# MachLedNhayTheoNhacNhieuCot.net
KiCad netlist of a schematic drawn in Altium Designer
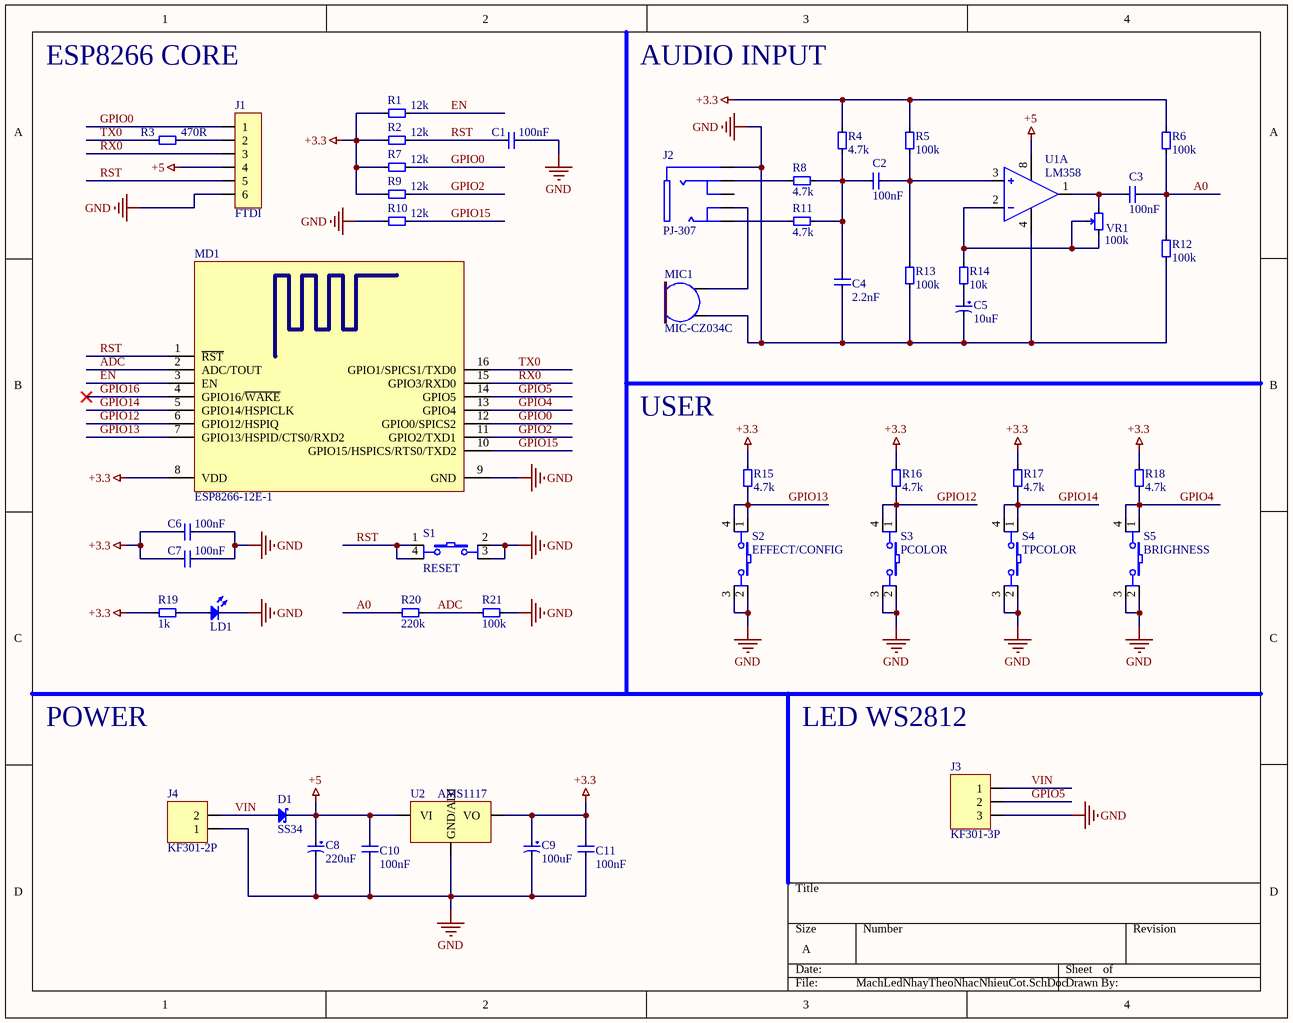
[diagram p0: MachLedNhayTheoNhacNhieuCot.SchDoc]

(export (version "E")
  (design (tool "Eeschema 10.0.6"))
  (components
    (comp (ref "C1")
      (value "100nF")
      (footprint "C-0805")
      (description "Cac Loai Tu Khong Phan Cuc")
      (libsource (lib "phatvu1294_Lib") (part "CAP"))
    )
    (comp (ref "C2")
      (value "100nF")
      (footprint "C-0805")
      (description "Cac Loai Tu Khong Phan Cuc")
      (libsource (lib "phatvu1294_Lib") (part "CAP"))
    )
    (comp (ref "C3")
      (value "100nF")
      (footprint "C-0805")
      (description "Cac Loai Tu Khong Phan Cuc")
      (libsource (lib "phatvu1294_Lib") (part "CAP"))
    )
    (comp (ref "C4")
      (value "2.2nF")
      (footprint "C-0805")
      (description "Cac Loai Tu Khong Phan Cuc")
      (libsource (lib "phatvu1294_Lib") (part "CAP"))
    )
    (comp (ref "C5")
      (value "10uF")
      (footprint "C-ELE-2-5X7MM")
      (description "Cac Loai Tu Hoa")
      (libsource (lib "phatvu1294_Lib") (part "CAP-ELE"))
    )
    (comp (ref "C6")
      (value "100nF")
      (footprint "C-0805")
      (description "Cac Loai Tu Khong Phan Cuc")
      (libsource (lib "phatvu1294_Lib") (part "CAP"))
    )
    (comp (ref "C7")
      (value "100nF")
      (footprint "C-0805")
      (description "Cac Loai Tu Khong Phan Cuc")
      (libsource (lib "phatvu1294_Lib") (part "CAP"))
    )
    (comp (ref "C8")
      (value "220uF")
      (footprint "C-ELE-2.5-6.3X12MM-A")
      (description "Cac Loai Tu Hoa")
      (libsource (lib "phatvu1294_Lib") (part "CAP-ELE"))
    )
    (comp (ref "C9")
      (value "100uF")
      (footprint "C-ELE-2.5-6.3X11MM-A")
      (description "Cac Loai Tu Hoa")
      (libsource (lib "phatvu1294_Lib") (part "CAP-ELE"))
    )
    (comp (ref "C10")
      (value "100nF")
      (footprint "C-0805")
      (description "Cac Loai Tu Khong Phan Cuc")
      (libsource (lib "phatvu1294_Lib") (part "CAP"))
    )
    (comp (ref "C11")
      (value "100nF")
      (footprint "C-0805")
      (description "Cac Loai Tu Khong Phan Cuc")
      (libsource (lib "phatvu1294_Lib") (part "CAP"))
    )
    (comp (ref "D1")
      (value "SS34")
      (footprint "DO-214AC-SMA")
      (description "Diode Schottky 1N5822 3A 40V Dan")
      (libsource (lib "phatvu1294_Lib") (part "SS34"))
    )
    (comp (ref "J1")
      (value "FTDI")
      (footprint "JP1X6M-2.54")
      (description "Jump Don 6 Chan 2.54mm")
      (libsource (lib "phatvu1294_Lib") (part "JP1X6-2.54"))
    )
    (comp (ref "J2")
      (value "PJ-307")
      (footprint "PJ-307")
      (description "Jack Ket Noi Audio 3.5MM")
      (libsource (lib "phatvu1294_Lib") (part "PJ-307"))
    )
    (comp (ref "J3")
      (value "KF301-3P")
      (footprint "KF301-3P-5.0")
      (description "Dau Ket Noi KF301 3 Chan")
      (libsource (lib "phatvu1294_Lib") (part "KF301-3P"))
    )
    (comp (ref "J4")
      (value "KF301-2P")
      (footprint "KF301-2P-5.0")
      (description "Dau Ket Noi KF301 2 Chan")
      (libsource (lib "phatvu1294_Lib") (part "KF301-2P"))
    )
    (comp (ref "LD1")
      (value "PWR")
      (footprint "LED-0805-RED")
      (description "Cac Loai LED Don")
      (libsource (lib "phatvu1294_Lib") (part "LED"))
    )
    (comp (ref "MD1")
      (value "ESP8266-12E-1")
      (footprint "ESP8266-12E-1")
      (description "Module ESP8266-12E")
      (libsource (lib "phatvu1294_Lib") (part "ESP8266-12E-1"))
    )
    (comp (ref "MIC1")
      (value "MIC-CZ034C")
      (footprint "MIC-CZ034C")
      (description "Microphone CZ034C")
      (libsource (lib "phatvu1294_Lib") (part "MIC-CZ034C"))
    )
    (comp (ref "R1")
      (value "12k")
      (footprint "R-0805")
      (description "Cac Loai Dien Tro")
      (libsource (lib "phatvu1294_Lib") (part "RES"))
    )
    (comp (ref "R2")
      (value "12k")
      (footprint "R-0805")
      (description "Cac Loai Dien Tro")
      (libsource (lib "phatvu1294_Lib") (part "RES"))
    )
    (comp (ref "R3")
      (value "470R")
      (footprint "R-0805")
      (description "Cac Loai Dien Tro")
      (libsource (lib "phatvu1294_Lib") (part "RES"))
    )
    (comp (ref "R4")
      (value "4.7k")
      (footprint "R-0805")
      (description "Cac Loai Dien Tro")
      (libsource (lib "phatvu1294_Lib") (part "RES"))
    )
    (comp (ref "R5")
      (value "100k")
      (footprint "R-0805")
      (description "Cac Loai Dien Tro")
      (libsource (lib "phatvu1294_Lib") (part "RES"))
    )
    (comp (ref "R6")
      (value "100k")
      (footprint "R-0805")
      (description "Cac Loai Dien Tro")
      (libsource (lib "phatvu1294_Lib") (part "RES"))
    )
    (comp (ref "R7")
      (value "12k")
      (footprint "R-0805")
      (description "Cac Loai Dien Tro")
      (libsource (lib "phatvu1294_Lib") (part "RES"))
    )
    (comp (ref "R8")
      (value "4.7k")
      (footprint "R-0805")
      (description "Cac Loai Dien Tro")
      (libsource (lib "phatvu1294_Lib") (part "RES"))
    )
    (comp (ref "R9")
      (value "12k")
      (footprint "R-0805")
      (description "Cac Loai Dien Tro")
      (libsource (lib "phatvu1294_Lib") (part "RES"))
    )
    (comp (ref "R10")
      (value "12k")
      (footprint "R-0805")
      (description "Cac Loai Dien Tro")
      (libsource (lib "phatvu1294_Lib") (part "RES"))
    )
    (comp (ref "R11")
      (value "4.7k")
      (footprint "R-0805")
      (description "Cac Loai Dien Tro")
      (libsource (lib "phatvu1294_Lib") (part "RES"))
    )
    (comp (ref "R12")
      (value "100k")
      (footprint "R-0805")
      (description "Cac Loai Dien Tro")
      (libsource (lib "phatvu1294_Lib") (part "RES"))
    )
    (comp (ref "R13")
      (value "100k")
      (footprint "R-0805")
      (description "Cac Loai Dien Tro")
      (libsource (lib "phatvu1294_Lib") (part "RES"))
    )
    (comp (ref "R14")
      (value "10k")
      (footprint "R-0805")
      (description "Cac Loai Dien Tro")
      (libsource (lib "phatvu1294_Lib") (part "RES"))
    )
    (comp (ref "R15")
      (value "4.7k")
      (footprint "R-0805")
      (description "Cac Loai Dien Tro")
      (libsource (lib "phatvu1294_Lib") (part "RES"))
    )
    (comp (ref "R16")
      (value "4.7k")
      (footprint "R-0805")
      (description "Cac Loai Dien Tro")
      (libsource (lib "phatvu1294_Lib") (part "RES"))
    )
    (comp (ref "R17")
      (value "4.7k")
      (footprint "R-0805")
      (description "Cac Loai Dien Tro")
      (libsource (lib "phatvu1294_Lib") (part "RES"))
    )
    (comp (ref "R18")
      (value "4.7k")
      (footprint "R-0805")
      (description "Cac Loai Dien Tro")
      (libsource (lib "phatvu1294_Lib") (part "RES"))
    )
    (comp (ref "R19")
      (value "1k")
      (footprint "R-0805")
      (description "Cac Loai Dien Tro")
      (libsource (lib "phatvu1294_Lib") (part "RES"))
    )
    (comp (ref "R20")
      (value "220k")
      (footprint "R-0805")
      (description "Cac Loai Dien Tro")
      (libsource (lib "phatvu1294_Lib") (part "RES"))
    )
    (comp (ref "R21")
      (value "100k")
      (footprint "R-0805")
      (description "Cac Loai Dien Tro")
      (libsource (lib "phatvu1294_Lib") (part "RES"))
    )
    (comp (ref "S1")
      (value "RESET")
      (footprint "SW4P-DIP-6X6MM")
      (description "Nut Nhan 4 Chan 6X6MM")
      (libsource (lib "phatvu1294_Lib") (part "SW4P-DIP-6X6MM"))
    )
    (comp (ref "S2")
      (value "EFFECT/CONFIG")
      (footprint "SW4P-DIP-6X6MM")
      (description "Nut Nhan 4 Chan 6X6MM")
      (libsource (lib "phatvu1294_Lib") (part "SW4P-DIP-6X6MM"))
    )
    (comp (ref "S3")
      (value "PCOLOR")
      (footprint "SW4P-DIP-6X6MM")
      (description "Nut Nhan 4 Chan 6X6MM")
      (libsource (lib "phatvu1294_Lib") (part "SW4P-DIP-6X6MM"))
    )
    (comp (ref "S4")
      (value "TPCOLOR")
      (footprint "SW4P-DIP-6X6MM")
      (description "Nut Nhan 4 Chan 6X6MM")
      (libsource (lib "phatvu1294_Lib") (part "SW4P-DIP-6X6MM"))
    )
    (comp (ref "S5")
      (value "BRIGHNESS")
      (footprint "SW4P-DIP-6X6MM")
      (description "Nut Nhan 4 Chan 6X6MM")
      (libsource (lib "phatvu1294_Lib") (part "SW4P-DIP-6X6MM"))
    )
    (comp (ref "U1")
      (value "LM358")
      (footprint "SO8-1.27-150MIL")
      (description "IC OPAM 2 Kenh")
      (libsource (lib "phatvu1294_Lib") (part "LM358"))
    )
    (comp (ref "U2")
      (value "AMS1117")
      (footprint "SOT223")
      (description "IC On Ap Tuyen Tinh AMS1117 1A")
      (libsource (lib "phatvu1294_Lib") (part "AMS1117"))
    )
    (comp (ref "VR1")
      (value "100k")
      (footprint "VR-ADJ-3362P")
      (description "Cac Loai Bien Tro")
      (libsource (lib "phatvu1294_Lib") (part "VRES"))
    )
  )
  (nets
    (net (code "1") (name "+3.3") (class "Default")
      (node (ref "C11") (pin "2") (pinfunction "2_2") (pintype "passive"))
      (node (ref "C6") (pin "2") (pinfunction "2_2") (pintype "passive"))
      (node (ref "C7") (pin "2") (pinfunction "2_2") (pintype "passive"))
      (node (ref "C9") (pin "1") (pinfunction "1_1") (pintype "passive"))
      (node (ref "MD1") (pin "8") (pinfunction "VDD_8") (pintype "power_in"))
      (node (ref "R1") (pin "1") (pinfunction "1_1") (pintype "passive"))
      (node (ref "R15") (pin "2") (pinfunction "2_2") (pintype "passive"))
      (node (ref "R16") (pin "2") (pinfunction "2_2") (pintype "passive"))
      (node (ref "R17") (pin "2") (pinfunction "2_2") (pintype "passive"))
      (node (ref "R18") (pin "2") (pinfunction "2_2") (pintype "passive"))
      (node (ref "R19") (pin "1") (pinfunction "1_1") (pintype "passive"))
      (node (ref "R2") (pin "1") (pinfunction "1_1") (pintype "passive"))
      (node (ref "R4") (pin "2") (pinfunction "2_2") (pintype "passive"))
      (node (ref "R5") (pin "2") (pinfunction "2_2") (pintype "passive"))
      (node (ref "R6") (pin "2") (pinfunction "2_2") (pintype "passive"))
      (node (ref "R7") (pin "1") (pinfunction "1_1") (pintype "passive"))
      (node (ref "R9") (pin "1") (pinfunction "1_1") (pintype "passive"))
      (node (ref "U2") (pin "2") (pinfunction "VO_2") (pintype "power_in"))
    )
    (net (code "2") (name "+5") (class "Default")
      (node (ref "C10") (pin "2") (pinfunction "2_2") (pintype "passive"))
      (node (ref "C8") (pin "1") (pinfunction "1_1") (pintype "passive"))
      (node (ref "D1") (pin "2") (pinfunction "2_2") (pintype "passive"))
      (node (ref "J1") (pin "4") (pinfunction "4_4") (pintype "passive"))
      (node (ref "U1") (pin "8") (pinfunction "V+_8") (pintype "power_in"))
      (node (ref "U2") (pin "3") (pinfunction "VI_3") (pintype "power_in"))
    )
    (net (code "3") (name "/A0") (class "Default")
      (node (ref "C3") (pin "2") (pinfunction "2_2") (pintype "passive"))
      (node (ref "R12") (pin "2") (pinfunction "2_2") (pintype "passive"))
      (node (ref "R20") (pin "1") (pinfunction "1_1") (pintype "passive"))
      (node (ref "R6") (pin "1") (pinfunction "1_1") (pintype "passive"))
    )
    (net (code "4") (name "/ADC") (class "Default")
      (node (ref "MD1") (pin "2") (pinfunction "ADC/TOUT_2") (pintype "passive"))
      (node (ref "R20") (pin "2") (pinfunction "2_2") (pintype "passive"))
      (node (ref "R21") (pin "1") (pinfunction "1_1") (pintype "passive"))
    )
    (net (code "5") (name "/EN") (class "Default")
      (node (ref "MD1") (pin "3") (pinfunction "EN_3") (pintype "passive"))
      (node (ref "R1") (pin "2") (pinfunction "2_2") (pintype "passive"))
    )
    (net (code "6") (name "/GPIO0") (class "Default")
      (node (ref "J1") (pin "1") (pinfunction "1_1") (pintype "passive"))
      (node (ref "MD1") (pin "12") (pinfunction "GPIO0/SPICS2_12") (pintype "passive"))
      (node (ref "R7") (pin "2") (pinfunction "2_2") (pintype "passive"))
    )
    (net (code "7") (name "/GPIO2") (class "Default")
      (node (ref "MD1") (pin "11") (pinfunction "GPIO2/TXD1_11") (pintype "passive"))
      (node (ref "R9") (pin "2") (pinfunction "2_2") (pintype "passive"))
    )
    (net (code "8") (name "/GPIO4") (class "Default")
      (node (ref "MD1") (pin "13") (pinfunction "GPIO4_13") (pintype "passive"))
      (node (ref "R18") (pin "1") (pinfunction "1_1") (pintype "passive"))
      (node (ref "S5") (pin "1") (pinfunction "1_1") (pintype "passive"))
      (node (ref "S5") (pin "4") (pinfunction "4_4") (pintype "passive"))
    )
    (net (code "9") (name "/GPIO5") (class "Default")
      (node (ref "J3") (pin "2") (pinfunction "2_2") (pintype "passive"))
      (node (ref "MD1") (pin "14") (pinfunction "GPIO5_14") (pintype "passive"))
    )
    (net (code "10") (name "/GPIO12") (class "Default")
      (node (ref "MD1") (pin "6") (pinfunction "GPIO12/HSPIQ_6") (pintype "passive"))
      (node (ref "R16") (pin "1") (pinfunction "1_1") (pintype "passive"))
      (node (ref "S3") (pin "1") (pinfunction "1_1") (pintype "passive"))
      (node (ref "S3") (pin "4") (pinfunction "4_4") (pintype "passive"))
    )
    (net (code "11") (name "/GPIO13") (class "Default")
      (node (ref "MD1") (pin "7") (pinfunction "GPIO13/HSPID/CTS0/RXD2_7") (pintype "passive"))
      (node (ref "R15") (pin "1") (pinfunction "1_1") (pintype "passive"))
      (node (ref "S2") (pin "1") (pinfunction "1_1") (pintype "passive"))
      (node (ref "S2") (pin "4") (pinfunction "4_4") (pintype "passive"))
    )
    (net (code "12") (name "/GPIO14") (class "Default")
      (node (ref "MD1") (pin "5") (pinfunction "GPIO14/HSPICLK_5") (pintype "passive"))
      (node (ref "R17") (pin "1") (pinfunction "1_1") (pintype "passive"))
      (node (ref "S4") (pin "1") (pinfunction "1_1") (pintype "passive"))
      (node (ref "S4") (pin "4") (pinfunction "4_4") (pintype "passive"))
    )
    (net (code "13") (name "/GPIO15") (class "Default")
      (node (ref "MD1") (pin "10") (pinfunction "GPIO15/HSPICS/RTS0/TXD2_10") (pintype "passive"))
      (node (ref "R10") (pin "2") (pinfunction "2_2") (pintype "passive"))
    )
    (net (code "14") (name "/GPIO16") (class "Default")
      (node (ref "MD1") (pin "4") (pinfunction "GPIO16/~{WAKE}_4") (pintype "passive+no_connect"))
    )
    (net (code "15") (name "/RST") (class "Default")
      (node (ref "C1") (pin "2") (pinfunction "2_2") (pintype "passive"))
      (node (ref "J1") (pin "5") (pinfunction "5_5") (pintype "passive"))
      (node (ref "MD1") (pin "1") (pinfunction "~{RST}_1") (pintype "passive"))
      (node (ref "R2") (pin "2") (pinfunction "2_2") (pintype "passive"))
      (node (ref "S1") (pin "1") (pinfunction "1_1") (pintype "passive"))
      (node (ref "S1") (pin "4") (pinfunction "4_4") (pintype "passive"))
    )
    (net (code "16") (name "/RX0") (class "Default")
      (node (ref "J1") (pin "3") (pinfunction "3_3") (pintype "passive"))
      (node (ref "MD1") (pin "15") (pinfunction "GPIO3/RXD0_15") (pintype "passive"))
    )
    (net (code "17") (name "/TX0") (class "Default")
      (node (ref "MD1") (pin "16") (pinfunction "GPIO1/SPICS1/TXD0_16") (pintype "passive"))
      (node (ref "R3") (pin "1") (pinfunction "1_1") (pintype "passive"))
    )
    (net (code "18") (name "/VIN") (class "Default")
      (node (ref "D1") (pin "1") (pinfunction "1_1") (pintype "passive"))
      (node (ref "J3") (pin "1") (pinfunction "1_1") (pintype "passive"))
      (node (ref "J4") (pin "2") (pinfunction "2_2") (pintype "passive"))
    )
    (net (code "19") (name "GND") (class "Default")
      (node (ref "C1") (pin "1") (pinfunction "1_1") (pintype "passive"))
      (node (ref "C10") (pin "1") (pinfunction "1_1") (pintype "passive"))
      (node (ref "C11") (pin "1") (pinfunction "1_1") (pintype "passive"))
      (node (ref "C4") (pin "2") (pinfunction "2_2") (pintype "passive"))
      (node (ref "C5") (pin "2") (pinfunction "2_2") (pintype "passive"))
      (node (ref "C6") (pin "1") (pinfunction "1_1") (pintype "passive"))
      (node (ref "C7") (pin "1") (pinfunction "1_1") (pintype "passive"))
      (node (ref "C8") (pin "2") (pinfunction "2_2") (pintype "passive"))
      (node (ref "C9") (pin "2") (pinfunction "2_2") (pintype "passive"))
      (node (ref "J1") (pin "6") (pinfunction "6_6") (pintype "passive"))
      (node (ref "J2") (pin "1") (pinfunction "1_1") (pintype "passive"))
      (node (ref "J3") (pin "3") (pinfunction "3_3") (pintype "passive"))
      (node (ref "J4") (pin "1") (pinfunction "1_1") (pintype "passive"))
      (node (ref "LD1") (pin "2") (pinfunction "2_2") (pintype "passive"))
      (node (ref "MD1") (pin "9") (pinfunction "GND_9") (pintype "power_in"))
      (node (ref "MIC1") (pin "1") (pinfunction "1_1") (pintype "passive"))
      (node (ref "R10") (pin "1") (pinfunction "1_1") (pintype "passive"))
      (node (ref "R12") (pin "1") (pinfunction "1_1") (pintype "passive"))
      (node (ref "R13") (pin "1") (pinfunction "1_1") (pintype "passive"))
      (node (ref "R21") (pin "2") (pinfunction "2_2") (pintype "passive"))
      (node (ref "S1") (pin "2") (pinfunction "2_2") (pintype "passive"))
      (node (ref "S1") (pin "3") (pinfunction "3_3") (pintype "passive"))
      (node (ref "S2") (pin "2") (pinfunction "2_2") (pintype "passive"))
      (node (ref "S2") (pin "3") (pinfunction "3_3") (pintype "passive"))
      (node (ref "S3") (pin "2") (pinfunction "2_2") (pintype "passive"))
      (node (ref "S3") (pin "3") (pinfunction "3_3") (pintype "passive"))
      (node (ref "S4") (pin "2") (pinfunction "2_2") (pintype "passive"))
      (node (ref "S4") (pin "3") (pinfunction "3_3") (pintype "passive"))
      (node (ref "S5") (pin "2") (pinfunction "2_2") (pintype "passive"))
      (node (ref "S5") (pin "3") (pinfunction "3_3") (pintype "passive"))
      (node (ref "U1") (pin "4") (pinfunction "V-_4") (pintype "power_in"))
      (node (ref "U2") (pin "1") (pinfunction "GND/ADJ_1") (pintype "power_in"))
    )
    (net (code "20") (name "Net-(C2-Pad1)") (class "Default")
      (node (ref "C2") (pin "1") (pinfunction "1_1") (pintype "passive"))
      (node (ref "C4") (pin "1") (pinfunction "1_1") (pintype "passive"))
      (node (ref "R11") (pin "1") (pinfunction "1_1") (pintype "passive"))
      (node (ref "R4") (pin "1") (pinfunction "1_1") (pintype "passive"))
      (node (ref "R8") (pin "1") (pinfunction "1_1") (pintype "passive"))
    )
    (net (code "21") (name "Net-(C5-Pad1)") (class "Default")
      (node (ref "C5") (pin "1") (pinfunction "1_1") (pintype "passive"))
      (node (ref "R14") (pin "1") (pinfunction "1_1") (pintype "passive"))
    )
    (net (code "22") (name "Net-(J1-Pad2)") (class "Default")
      (node (ref "J1") (pin "2") (pinfunction "2_2") (pintype "passive"))
      (node (ref "R3") (pin "2") (pinfunction "2_2") (pintype "passive"))
    )
    (net (code "23") (name "Net-(J2-Pad2)") (class "Default")
      (node (ref "J2") (pin "2") (pinfunction "2_2") (pintype "passive"))
      (node (ref "R8") (pin "2") (pinfunction "2_2") (pintype "passive"))
    )
    (net (code "24") (name "Net-(J2-Pad4)") (class "Default")
      (node (ref "J2") (pin "4") (pinfunction "4_4") (pintype "passive"))
      (node (ref "MIC1") (pin "2") (pinfunction "2_2") (pintype "passive"))
    )
    (net (code "25") (name "Net-(J2-Pad5)") (class "Default")
      (node (ref "J2") (pin "5") (pinfunction "5_5") (pintype "passive"))
      (node (ref "R11") (pin "2") (pinfunction "2_2") (pintype "passive"))
    )
    (net (code "26") (name "Net-(LD1-Pad1)") (class "Default")
      (node (ref "LD1") (pin "1") (pinfunction "1_1") (pintype "passive"))
      (node (ref "R19") (pin "2") (pinfunction "2_2") (pintype "passive"))
    )
    (net (code "27") (name "Net-(U1A-+INA)") (class "Default")
      (node (ref "C2") (pin "2") (pinfunction "2_2") (pintype "passive"))
      (node (ref "R13") (pin "2") (pinfunction "2_2") (pintype "passive"))
      (node (ref "R5") (pin "1") (pinfunction "1_1") (pintype "passive"))
      (node (ref "U1") (pin "3") (pinfunction "+INA_3") (pintype "passive"))
    )
    (net (code "28") (name "Net-(U1A--INA)") (class "Default")
      (node (ref "R14") (pin "2") (pinfunction "2_2") (pintype "passive"))
      (node (ref "U1") (pin "2") (pinfunction "-INA_2") (pintype "passive"))
      (node (ref "VR1") (pin "1") (pinfunction "1_1") (pintype "passive"))
      (node (ref "VR1") (pin "2") (pinfunction "2_2") (pintype "passive"))
    )
    (net (code "29") (name "Net-(U1A-OUTA)") (class "Default")
      (node (ref "C3") (pin "1") (pinfunction "1_1") (pintype "passive"))
      (node (ref "U1") (pin "1") (pinfunction "OUTA_1") (pintype "passive"))
      (node (ref "VR1") (pin "3") (pinfunction "3_3") (pintype "passive"))
    )
    (net (code "30") (name "unconnected-(J2-Pad3)") (class "Default")
      (node (ref "J2") (pin "3") (pinfunction "3_3") (pintype "passive"))
    )
  )
)
